# tick-wifi-mini-mk-1_0.net
KiCad netlist of a schematic drawn in EAGLE
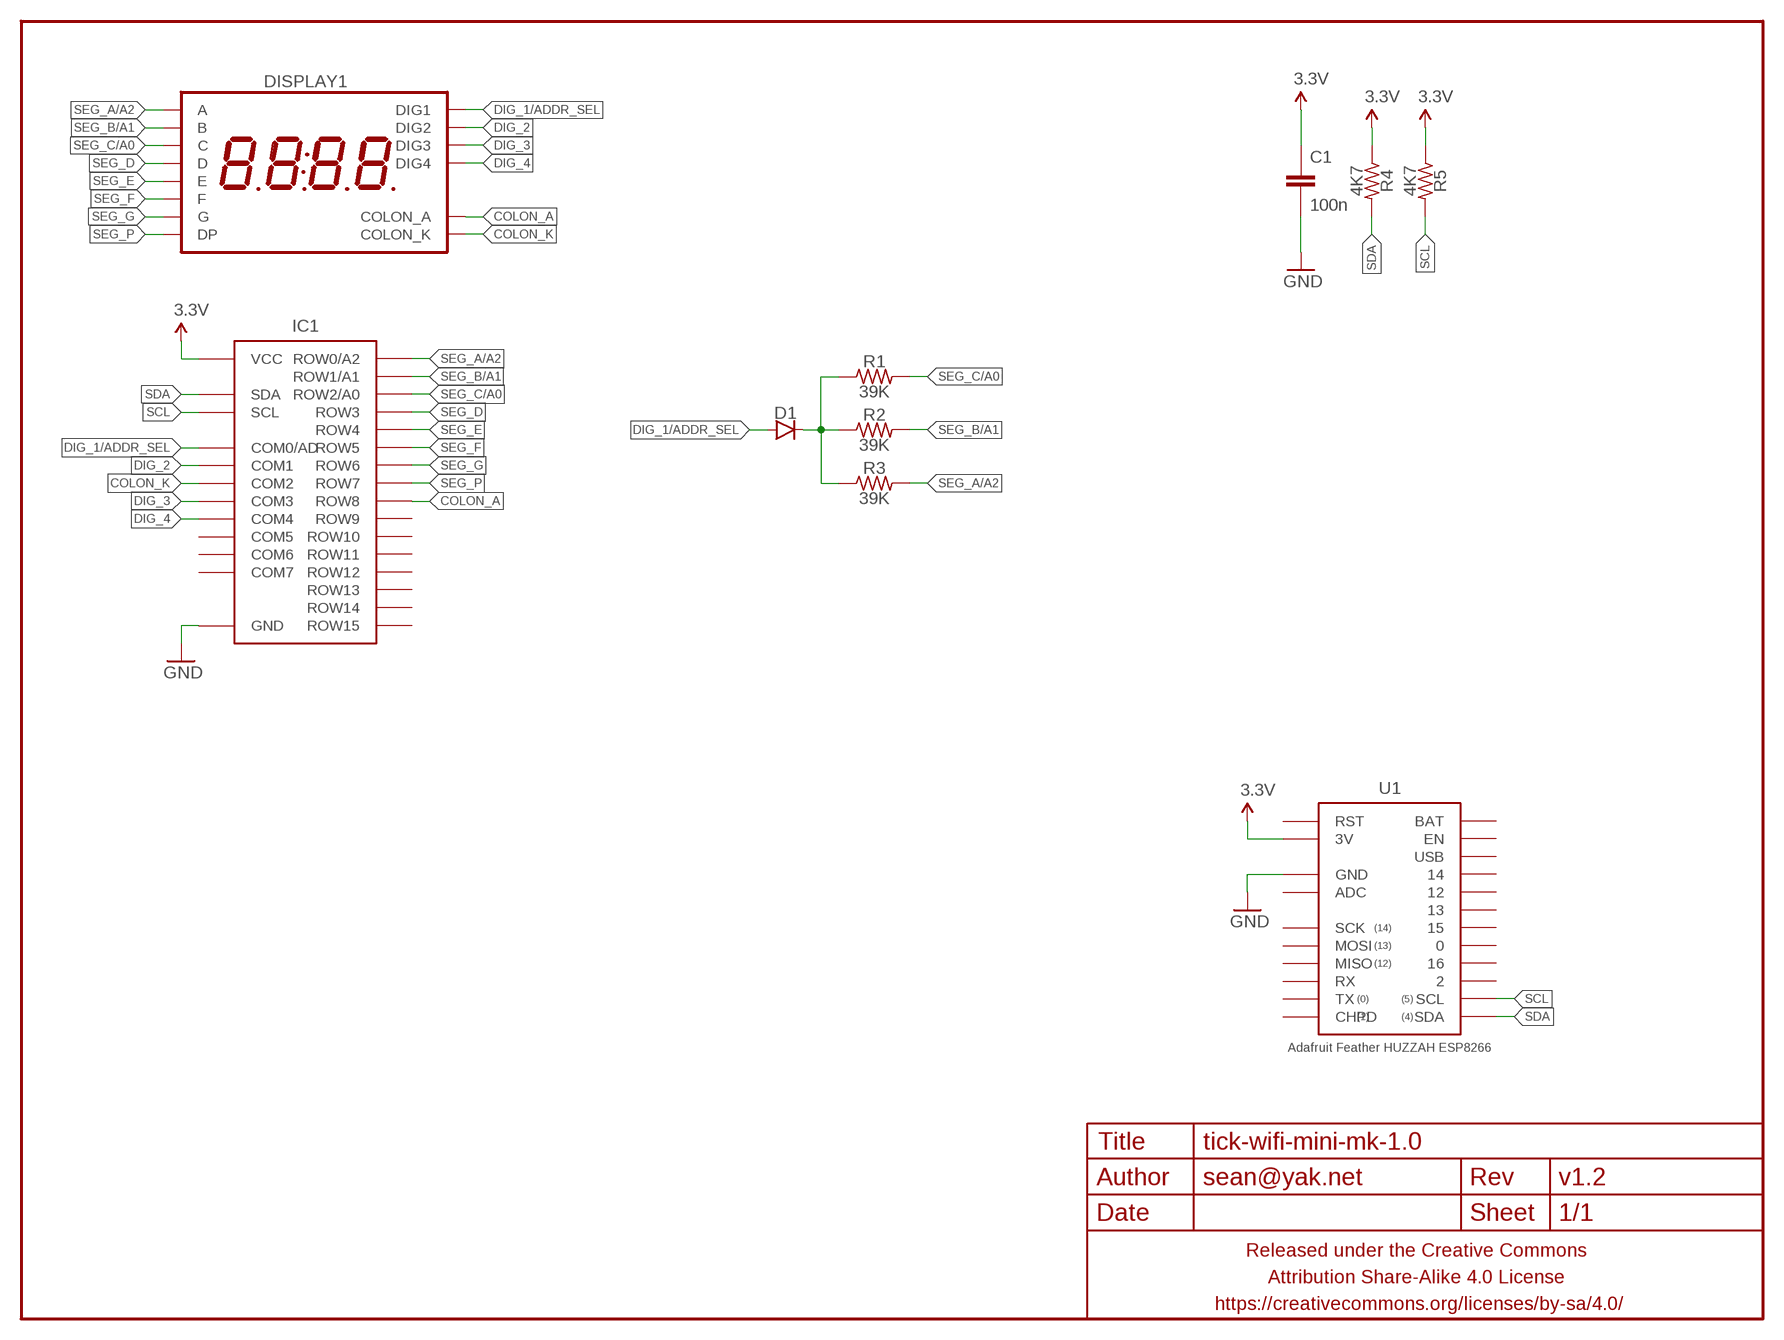
[diagram p0: schematic, sheet 1]

(export (version "E")
  (design (tool "Eeschema 10.0.6"))
  (components
    (comp (ref "C1")
      (value "100n")
      (footprint "eagle-import:C0603")
      (libsource (lib "eagle-import") (part "CAPACITOR-CERAMICC0603"))
    )
    (comp (ref "D1")
      (value "DIODESOD123")
      (footprint "eagle-import:SOD123")
      (libsource (lib "eagle-import") (part "DIODESOD123"))
    )
    (comp (ref "DISPLAY1")
      (value "7SEG_4DIGIT_COLON14.2MM-CC")
      (footprint "eagle-import:7SEG_4DIG_0.56IN_14MM_ADAFRUIT")
      (libsource (lib "eagle-import") (part "7SEG_4DIGIT_COLON14.2MM-CC"))
    )
    (comp (ref "FRAME1")
      (value "FRAME-LETTERNO_PACKAGE")
      (footprint "eagle-import:DUMMY")
      (fields (field (name "DESIGNER") "sean@yak.net") (field (name "VERSION") "v1.2"))
      (libsource (lib "eagle-import") (part "FRAME-LETTERNO_PACKAGE"))
    )
    (comp (ref "IC1")
      (value "HT16K33")
      (footprint "eagle-import:SOIC28W")
      (libsource (lib "eagle-import") (part "HT16K33-28SOIC28W"))
    )
    (comp (ref "R1")
      (value "39K")
      (footprint "eagle-import:R0603")
      (libsource (lib "eagle-import") (part "RESISTORR0603"))
    )
    (comp (ref "R2")
      (value "39K")
      (footprint "eagle-import:R0603")
      (libsource (lib "eagle-import") (part "RESISTORR0603"))
    )
    (comp (ref "R3")
      (value "39K")
      (footprint "eagle-import:R0603")
      (libsource (lib "eagle-import") (part "RESISTORR0603"))
    )
    (comp (ref "R4")
      (value "4K7")
      (footprint "eagle-import:R0603")
      (libsource (lib "eagle-import") (part "RESISTORR0603"))
    )
    (comp (ref "R5")
      (value "4K7")
      (footprint "eagle-import:R0603")
      (libsource (lib "eagle-import") (part "RESISTORR0603"))
    )
    (comp (ref "U1")
      (value "Adafruit Feather HUZZAH ESP8266")
      (footprint "eagle-import:ADAFRUIT_FEATHER_HUZZAH_NOSILK")
      (libsource (lib "eagle-import") (part "ADAFRUIT_FEATHER_HUZZAH_ESP8266NOSILK"))
    )
  )
  (nets
    (net (code "1") (name "3.3V") (class "Default")
      (node (ref "C1") (pin "1") (pinfunction "1_1") (pintype "passive"))
      (node (ref "IC1") (pin "28") (pinfunction "VCC_28") (pintype "bidirectional"))
      (node (ref "R4") (pin "1") (pinfunction "1_1") (pintype "passive"))
      (node (ref "R5") (pin "1") (pinfunction "1_1") (pintype "passive"))
      (node (ref "U1") (pin "3V") (pinfunction "3V_3V") (pintype "bidirectional"))
    )
    (net (code "2") (name "COLON_A") (class "Default")
      (node (ref "DISPLAY1") (pin "P$8") (pinfunction "COLON_A_P$8") (pintype "passive"))
      (node (ref "IC1") (pin "17") (pinfunction "ROW8_17") (pintype "bidirectional"))
    )
    (net (code "3") (name "COLON_K") (class "Default")
      (node (ref "DISPLAY1") (pin "P$7") (pinfunction "COLON_K_P$7") (pintype "passive"))
      (node (ref "IC1") (pin "4") (pinfunction "COM2_4") (pintype "bidirectional"))
    )
    (net (code "4") (name "DIG_1{slash}ADDR_SEL") (class "Default")
      (node (ref "D1") (pin "A") (pinfunction "A_A") (pintype "passive"))
      (node (ref "DISPLAY1") (pin "P$14") (pinfunction "DIG1_P$14") (pintype "passive"))
      (node (ref "IC1") (pin "2") (pinfunction "COM0/AD_2") (pintype "bidirectional"))
    )
    (net (code "5") (name "DIG_2") (class "Default")
      (node (ref "DISPLAY1") (pin "P$11") (pinfunction "DIG2_P$11") (pintype "passive"))
      (node (ref "IC1") (pin "3") (pinfunction "COM1_3") (pintype "bidirectional"))
    )
    (net (code "6") (name "DIG_3") (class "Default")
      (node (ref "DISPLAY1") (pin "P$10") (pinfunction "DIG3_P$10") (pintype "passive"))
      (node (ref "IC1") (pin "5") (pinfunction "COM3_5") (pintype "bidirectional"))
    )
    (net (code "7") (name "DIG_4") (class "Default")
      (node (ref "DISPLAY1") (pin "P$6") (pinfunction "DIG4_P$6") (pintype "passive"))
      (node (ref "IC1") (pin "6") (pinfunction "COM4_6") (pintype "bidirectional"))
    )
    (net (code "8") (name "GND") (class "Default")
      (node (ref "C1") (pin "2") (pinfunction "2_2") (pintype "passive"))
      (node (ref "IC1") (pin "1") (pinfunction "GND_1") (pintype "bidirectional"))
      (node (ref "U1") (pin "GND@0") (pinfunction "GND_GND@0") (pintype "bidirectional"))
    )
    (net (code "9") (name "Net-(D1-PadC)") (class "Default")
      (node (ref "D1") (pin "C") (pinfunction "C_C") (pintype "passive"))
      (node (ref "R1") (pin "1") (pinfunction "1_1") (pintype "passive"))
      (node (ref "R2") (pin "1") (pinfunction "1_1") (pintype "passive"))
      (node (ref "R3") (pin "1") (pinfunction "1_1") (pintype "passive"))
    )
    (net (code "10") (name "SCL") (class "Default")
      (node (ref "IC1") (pin "26") (pinfunction "SCL_26") (pintype "bidirectional"))
      (node (ref "R5") (pin "2") (pinfunction "2_2") (pintype "passive"))
      (node (ref "U1") (pin "SCL") (pinfunction "SCL_SCL") (pintype "bidirectional"))
    )
    (net (code "11") (name "SDA") (class "Default")
      (node (ref "IC1") (pin "27") (pinfunction "SDA_27") (pintype "bidirectional"))
      (node (ref "R4") (pin "2") (pinfunction "2_2") (pintype "passive"))
      (node (ref "U1") (pin "SDA") (pinfunction "SDA_SDA") (pintype "bidirectional"))
    )
    (net (code "12") (name "SEG_A{slash}A2") (class "Default")
      (node (ref "DISPLAY1") (pin "P$13") (pinfunction "A_P$13") (pintype "passive"))
      (node (ref "IC1") (pin "25") (pinfunction "ROW0/A2_25") (pintype "bidirectional"))
      (node (ref "R3") (pin "2") (pinfunction "2_2") (pintype "passive"))
    )
    (net (code "13") (name "SEG_B{slash}A1") (class "Default")
      (node (ref "DISPLAY1") (pin "P$9") (pinfunction "B_P$9") (pintype "passive"))
      (node (ref "IC1") (pin "24") (pinfunction "ROW1/A1_24") (pintype "bidirectional"))
      (node (ref "R2") (pin "2") (pinfunction "2_2") (pintype "passive"))
    )
    (net (code "14") (name "SEG_C{slash}A0") (class "Default")
      (node (ref "DISPLAY1") (pin "P$4") (pinfunction "C_P$4") (pintype "passive"))
      (node (ref "IC1") (pin "23") (pinfunction "ROW2/A0_23") (pintype "bidirectional"))
      (node (ref "R1") (pin "2") (pinfunction "2_2") (pintype "passive"))
    )
    (net (code "15") (name "SEG_D") (class "Default")
      (node (ref "DISPLAY1") (pin "P$2") (pinfunction "D_P$2") (pintype "passive"))
      (node (ref "IC1") (pin "22") (pinfunction "ROW3_22") (pintype "bidirectional"))
    )
    (net (code "16") (name "SEG_E") (class "Default")
      (node (ref "DISPLAY1") (pin "P$1") (pinfunction "E_P$1") (pintype "passive"))
      (node (ref "IC1") (pin "21") (pinfunction "ROW4_21") (pintype "bidirectional"))
    )
    (net (code "17") (name "SEG_F") (class "Default")
      (node (ref "DISPLAY1") (pin "P$12") (pinfunction "F_P$12") (pintype "passive"))
      (node (ref "IC1") (pin "20") (pinfunction "ROW5_20") (pintype "bidirectional"))
    )
    (net (code "18") (name "SEG_G") (class "Default")
      (node (ref "DISPLAY1") (pin "P$5") (pinfunction "G_P$5") (pintype "passive"))
      (node (ref "IC1") (pin "19") (pinfunction "ROW6_19") (pintype "bidirectional"))
    )
    (net (code "19") (name "SEG_P") (class "Default")
      (node (ref "DISPLAY1") (pin "P$3") (pinfunction "DP_P$3") (pintype "passive"))
      (node (ref "IC1") (pin "18") (pinfunction "ROW7_18") (pintype "bidirectional"))
    )
    (net (code "20") (name "unconnected-(IC1-COM5-Pad7)") (class "Default")
      (node (ref "IC1") (pin "7") (pinfunction "COM5_7") (pintype "bidirectional"))
    )
    (net (code "21") (name "unconnected-(IC1-COM6-Pad8)") (class "Default")
      (node (ref "IC1") (pin "8") (pinfunction "COM6_8") (pintype "bidirectional"))
    )
    (net (code "22") (name "unconnected-(IC1-COM7-Pad9)") (class "Default")
      (node (ref "IC1") (pin "9") (pinfunction "COM7_9") (pintype "bidirectional"))
    )
    (net (code "23") (name "unconnected-(IC1-ROW9-Pad16)") (class "Default")
      (node (ref "IC1") (pin "16") (pinfunction "ROW9_16") (pintype "bidirectional"))
    )
    (net (code "24") (name "unconnected-(IC1-ROW10-Pad15)") (class "Default")
      (node (ref "IC1") (pin "15") (pinfunction "ROW10_15") (pintype "bidirectional"))
    )
    (net (code "25") (name "unconnected-(IC1-ROW11-Pad14)") (class "Default")
      (node (ref "IC1") (pin "14") (pinfunction "ROW11_14") (pintype "bidirectional"))
    )
    (net (code "26") (name "unconnected-(IC1-ROW12-Pad13)") (class "Default")
      (node (ref "IC1") (pin "13") (pinfunction "ROW12_13") (pintype "bidirectional"))
    )
    (net (code "27") (name "unconnected-(IC1-ROW13-Pad12)") (class "Default")
      (node (ref "IC1") (pin "12") (pinfunction "ROW13_12") (pintype "bidirectional"))
    )
    (net (code "28") (name "unconnected-(IC1-ROW14-Pad11)") (class "Default")
      (node (ref "IC1") (pin "11") (pinfunction "ROW14_11") (pintype "bidirectional"))
    )
    (net (code "29") (name "unconnected-(IC1-ROW15-Pad10)") (class "Default")
      (node (ref "IC1") (pin "10") (pinfunction "ROW15_10") (pintype "bidirectional"))
    )
    (net (code "30") (name "unconnected-(U1-Pad0)") (class "Default")
      (node (ref "U1") (pin "0") (pinfunction "0_0") (pintype "bidirectional"))
    )
    (net (code "31") (name "unconnected-(U1-Pad2)") (class "Default")
      (node (ref "U1") (pin "2") (pinfunction "2_2") (pintype "bidirectional"))
    )
    (net (code "32") (name "unconnected-(U1-Pad12)") (class "Default")
      (node (ref "U1") (pin "12") (pinfunction "12_12") (pintype "bidirectional"))
    )
    (net (code "33") (name "unconnected-(U1-Pad13)") (class "Default")
      (node (ref "U1") (pin "13") (pinfunction "13_13") (pintype "bidirectional"))
    )
    (net (code "34") (name "unconnected-(U1-Pad14)") (class "Default")
      (node (ref "U1") (pin "14") (pinfunction "14_14") (pintype "bidirectional"))
    )
    (net (code "35") (name "unconnected-(U1-Pad15)") (class "Default")
      (node (ref "U1") (pin "15") (pinfunction "15_15") (pintype "bidirectional"))
    )
    (net (code "36") (name "unconnected-(U1-Pad16)") (class "Default")
      (node (ref "U1") (pin "16") (pinfunction "16_16") (pintype "bidirectional"))
    )
    (net (code "37") (name "unconnected-(U1-PadADC)") (class "Default")
      (node (ref "U1") (pin "ADC") (pinfunction "ADC_ADC") (pintype "bidirectional"))
    )
    (net (code "38") (name "unconnected-(U1-PadBAT)") (class "Default")
      (node (ref "U1") (pin "BAT") (pinfunction "BAT_BAT") (pintype "bidirectional"))
    )
    (net (code "39") (name "unconnected-(U1-PadCHPD)") (class "Default")
      (node (ref "U1") (pin "CHPD") (pinfunction "CHPD_CHPD") (pintype "bidirectional"))
    )
    (net (code "40") (name "unconnected-(U1-PadEN)") (class "Default")
      (node (ref "U1") (pin "EN") (pinfunction "EN_EN") (pintype "bidirectional"))
    )
    (net (code "41") (name "unconnected-(U1-PadMISO)") (class "Default")
      (node (ref "U1") (pin "MISO") (pinfunction "MISO_MISO") (pintype "bidirectional"))
    )
    (net (code "42") (name "unconnected-(U1-PadMOSI)") (class "Default")
      (node (ref "U1") (pin "MOSI") (pinfunction "MOSI_MOSI") (pintype "bidirectional"))
    )
    (net (code "43") (name "unconnected-(U1-PadRST)") (class "Default")
      (node (ref "U1") (pin "RST") (pinfunction "RST_RST") (pintype "bidirectional"))
    )
    (net (code "44") (name "unconnected-(U1-PadRX)") (class "Default")
      (node (ref "U1") (pin "RX") (pinfunction "RX_RX") (pintype "bidirectional"))
    )
    (net (code "45") (name "unconnected-(U1-PadSCK)") (class "Default")
      (node (ref "U1") (pin "SCK") (pinfunction "SCK_SCK") (pintype "bidirectional"))
    )
    (net (code "46") (name "unconnected-(U1-PadTX)") (class "Default")
      (node (ref "U1") (pin "TX") (pinfunction "TX_TX") (pintype "bidirectional"))
    )
    (net (code "47") (name "unconnected-(U1-PadUSB)") (class "Default")
      (node (ref "U1") (pin "USB") (pinfunction "USB_USB") (pintype "bidirectional"))
    )
  )
)
